# 4-IN-OPTPO-4-OUT.net
KiCad netlist of a schematic drawn in EAGLE
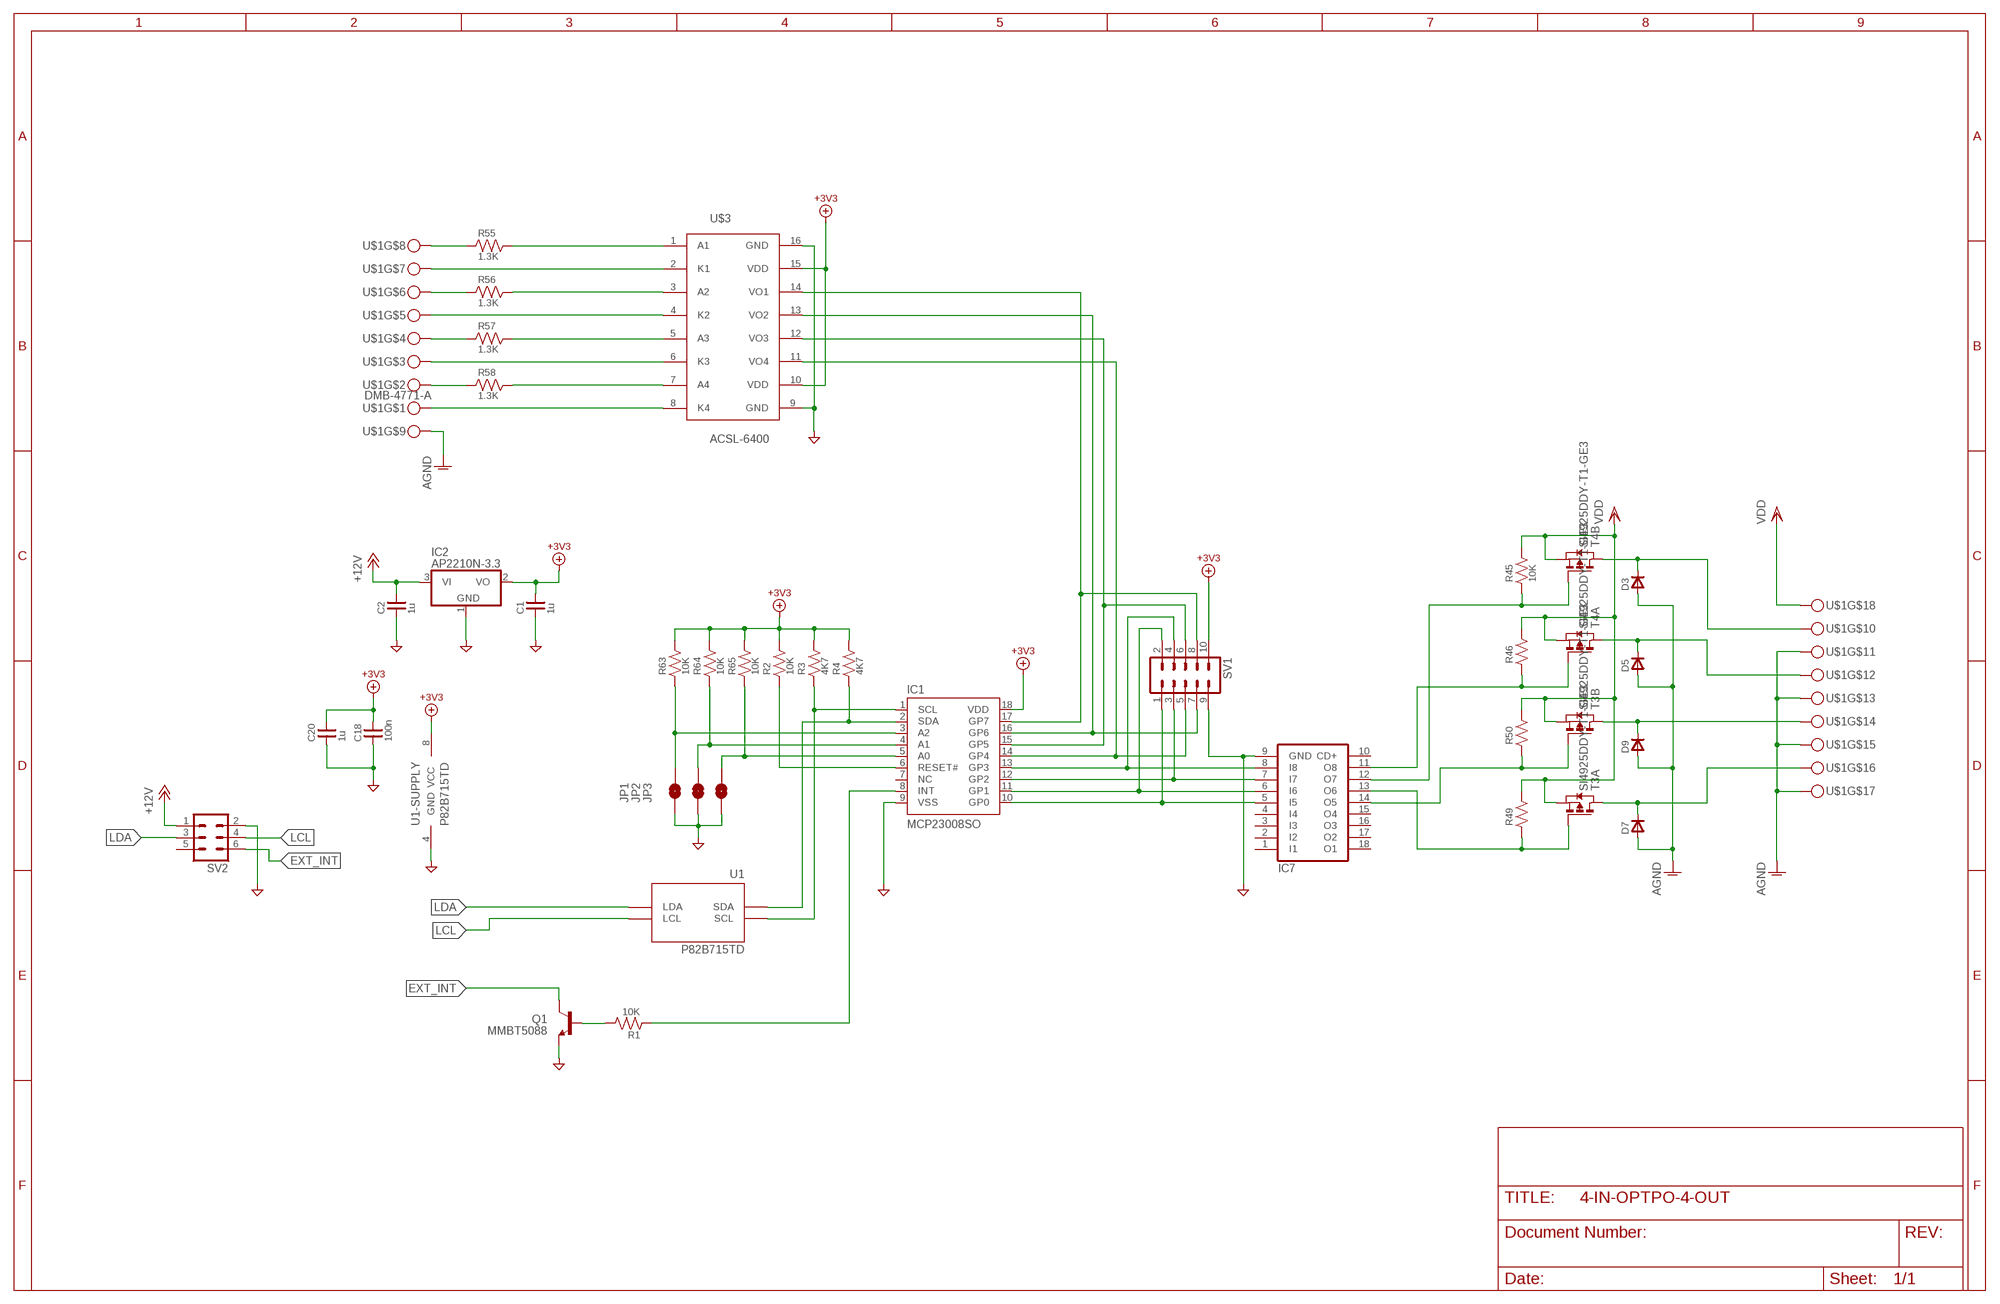
[diagram p0: schematic, sheet 1]

(export (version "E")
  (design (tool "Eeschema 10.0.6"))
  (components
    (comp (ref "C1")
      (value "1u")
      (footprint "eagle-import:C0805")
      (libsource (lib "eagle-import") (part "C0805"))
    )
    (comp (ref "C2")
      (value "1u")
      (footprint "eagle-import:C0805")
      (libsource (lib "eagle-import") (part "C0805"))
    )
    (comp (ref "C18")
      (value "100n")
      (footprint "eagle-import:C0805")
      (libsource (lib "eagle-import") (part "C0805"))
    )
    (comp (ref "C20")
      (value "1u")
      (footprint "eagle-import:C0805")
      (libsource (lib "eagle-import") (part "C0805"))
    )
    (comp (ref "D3")
      (value "DSMA")
      (footprint "eagle-import:DSMA")
      (libsource (lib "eagle-import") (part "DSMA"))
    )
    (comp (ref "D5")
      (value "DSMA")
      (footprint "eagle-import:DSMA")
      (libsource (lib "eagle-import") (part "DSMA"))
    )
    (comp (ref "D7")
      (value "DSMA")
      (footprint "eagle-import:DSMA")
      (libsource (lib "eagle-import") (part "DSMA"))
    )
    (comp (ref "D9")
      (value "DSMA")
      (footprint "eagle-import:DSMA")
      (libsource (lib "eagle-import") (part "DSMA"))
    )
    (comp (ref "IC1")
      (value "MCP23008SO")
      (footprint "eagle-import:SO-18W")
      (libsource (lib "eagle-import") (part "MCP23008SO"))
    )
    (comp (ref "IC2")
      (value "AP2210N-3.3")
      (footprint "eagle-import:SOT23")
      (libsource (lib "eagle-import") (part "MCP1703CB"))
    )
    (comp (ref "IC7")
      (value "ULN2803A")
      (footprint "eagle-import:SO18W")
      (libsource (lib "eagle-import") (part "ULN2803A"))
    )
    (comp (ref "JP1")
      (value "JUMPER-PAD-2-NOYES_SILK")
      (footprint "eagle-import:PAD-JUMPER-2-NO_YES_SILK")
      (libsource (lib "eagle-import") (part "JUMPER-PAD-2-NOYES_SILK"))
    )
    (comp (ref "JP2")
      (value "JUMPER-PAD-2-NOYES_SILK")
      (footprint "eagle-import:PAD-JUMPER-2-NO_YES_SILK")
      (libsource (lib "eagle-import") (part "JUMPER-PAD-2-NOYES_SILK"))
    )
    (comp (ref "JP3")
      (value "JUMPER-PAD-2-NOYES_SILK")
      (footprint "eagle-import:PAD-JUMPER-2-NO_YES_SILK")
      (libsource (lib "eagle-import") (part "JUMPER-PAD-2-NOYES_SILK"))
    )
    (comp (ref "Q1")
      (value "MMBT5088")
      (footprint "eagle-import:SOT23-3")
      (libsource (lib "eagle-import") (part "TRANSISTOR_NPNMMBT5088"))
    )
    (comp (ref "R1")
      (value "10K")
      (footprint "eagle-import:R0805")
      (libsource (lib "eagle-import") (part "RU0805"))
    )
    (comp (ref "R2")
      (value "10K")
      (footprint "eagle-import:R0805")
      (libsource (lib "eagle-import") (part "RU0805"))
    )
    (comp (ref "R3")
      (value "4K7")
      (footprint "eagle-import:R0805")
      (libsource (lib "eagle-import") (part "RU0805"))
    )
    (comp (ref "R4")
      (value "4K7")
      (footprint "eagle-import:R0805")
      (libsource (lib "eagle-import") (part "RU0805"))
    )
    (comp (ref "R45")
      (value "10K")
      (footprint "eagle-import:R0805")
      (libsource (lib "eagle-import") (part "RU0805"))
    )
    (comp (ref "R46")
      (value "RU0805")
      (footprint "eagle-import:R0805")
      (libsource (lib "eagle-import") (part "RU0805"))
    )
    (comp (ref "R49")
      (value "RU0805")
      (footprint "eagle-import:R0805")
      (libsource (lib "eagle-import") (part "RU0805"))
    )
    (comp (ref "R50")
      (value "RU0805")
      (footprint "eagle-import:R0805")
      (libsource (lib "eagle-import") (part "RU0805"))
    )
    (comp (ref "R55")
      (value "1.3K")
      (footprint "eagle-import:R0805")
      (libsource (lib "eagle-import") (part "RU0805"))
    )
    (comp (ref "R56")
      (value "1.3K")
      (footprint "eagle-import:R0805")
      (libsource (lib "eagle-import") (part "RU0805"))
    )
    (comp (ref "R57")
      (value "1.3K")
      (footprint "eagle-import:R0805")
      (libsource (lib "eagle-import") (part "RU0805"))
    )
    (comp (ref "R58")
      (value "1.3K")
      (footprint "eagle-import:R0805")
      (libsource (lib "eagle-import") (part "RU0805"))
    )
    (comp (ref "R63")
      (value "10K")
      (footprint "eagle-import:R0805")
      (libsource (lib "eagle-import") (part "RU0805"))
    )
    (comp (ref "R64")
      (value "10K")
      (footprint "eagle-import:R0805")
      (libsource (lib "eagle-import") (part "RU0805"))
    )
    (comp (ref "R65")
      (value "10K")
      (footprint "eagle-import:R0805")
      (libsource (lib "eagle-import") (part "RU0805"))
    )
    (comp (ref "SV1")
      (value "ML10")
      (footprint "eagle-import:ML10")
      (libsource (lib "eagle-import") (part "ML10"))
    )
    (comp (ref "SV2")
      (value "ML6")
      (footprint "eagle-import:ML6")
      (libsource (lib "eagle-import") (part "ML6"))
    )
    (comp (ref "T3")
      (value "SI4925DDY-T1-GE3")
      (footprint "eagle-import:SO8")
      (libsource (lib "eagle-import") (part "PMOS2SO8"))
    )
    (comp (ref "T4")
      (value "SI4925DDY-T1-GE3")
      (footprint "eagle-import:SO8")
      (libsource (lib "eagle-import") (part "PMOS2SO8"))
    )
    (comp (ref "U$1")
      (value "DMB-4771-A")
      (footprint "eagle-import:DMB-4771-A-PKG")
      (libsource (lib "eagle-import") (part "DMB-4771-A"))
    )
    (comp (ref "U$3")
      (value "ACSL-6400")
      (footprint "eagle-import:SO16")
      (libsource (lib "eagle-import") (part "ACSL-6400"))
    )
    (comp (ref "U1")
      (value "P82B715TD")
      (footprint "eagle-import:SOIC-8")
      (fields (field (name "MANUFACTURER") "NXP Semiconductors") (field (name "PART_NUMBER") "P82B715TD,118"))
      (libsource (lib "eagle-import") (part "P82B715?TD"))
    )
  )
  (nets
    (net (code "1") (name "+12V") (class "Default")
      (node (ref "C2") (pin "2") (pinfunction "2_2") (pintype "passive"))
      (node (ref "IC2") (pin "3") (pinfunction "VI_3") (pintype "input"))
      (node (ref "SV2") (pin "1") (pinfunction "1_1") (pintype "passive"))
    )
    (net (code "2") (name "AGND") (class "Default")
      (node (ref "D3") (pin "A") (pinfunction "A_A") (pintype "passive"))
      (node (ref "D5") (pin "A") (pinfunction "A_A") (pintype "passive"))
      (node (ref "D7") (pin "A") (pinfunction "A_A") (pintype "passive"))
      (node (ref "D9") (pin "A") (pinfunction "A_A") (pintype "passive"))
      (node (ref "U$1") (pin "P$11") (pinfunction "KL_P$11") (pintype "passive"))
      (node (ref "U$1") (pin "P$13") (pinfunction "KL_P$13") (pintype "passive"))
      (node (ref "U$1") (pin "P$15") (pinfunction "KL_P$15") (pintype "passive"))
      (node (ref "U$1") (pin "P$17") (pinfunction "KL_P$17") (pintype "passive"))
      (node (ref "U$1") (pin "P$9") (pinfunction "KL_P$9") (pintype "passive"))
    )
    (net (code "3") (name "EXT_INT") (class "Default")
      (node (ref "Q1") (pin "3") (pinfunction "C_3") (pintype "passive"))
      (node (ref "SV2") (pin "6") (pinfunction "6_6") (pintype "passive"))
    )
    (net (code "4") (name "LCL") (class "Default")
      (node (ref "SV2") (pin "4") (pinfunction "4_4") (pintype "passive"))
      (node (ref "U1") (pin "2") (pinfunction "LCL_2") (pintype "bidirectional"))
    )
    (net (code "5") (name "LDA") (class "Default")
      (node (ref "SV2") (pin "3") (pinfunction "3_3") (pintype "passive"))
      (node (ref "U1") (pin "7") (pinfunction "LDA_7") (pintype "bidirectional"))
    )
    (net (code "6") (name "Net-(IC1-A0)") (class "Default")
      (node (ref "IC1") (pin "5") (pinfunction "A0_5") (pintype "input"))
      (node (ref "JP3") (pin "2") (pinfunction "2_2") (pintype "passive"))
      (node (ref "R65") (pin "1") (pinfunction "1_1") (pintype "passive"))
    )
    (net (code "7") (name "Net-(IC1-A1)") (class "Default")
      (node (ref "IC1") (pin "4") (pinfunction "A1_4") (pintype "input"))
      (node (ref "JP2") (pin "2") (pinfunction "2_2") (pintype "passive"))
      (node (ref "R64") (pin "1") (pinfunction "1_1") (pintype "passive"))
    )
    (net (code "8") (name "Net-(IC1-A2)") (class "Default")
      (node (ref "IC1") (pin "3") (pinfunction "A2_3") (pintype "input"))
      (node (ref "JP1") (pin "2") (pinfunction "2_2") (pintype "passive"))
      (node (ref "R63") (pin "1") (pinfunction "1_1") (pintype "passive"))
    )
    (net (code "9") (name "Net-(IC1-GP0)") (class "Default")
      (node (ref "IC1") (pin "10") (pinfunction "GP0_10") (pintype "bidirectional"))
      (node (ref "IC7") (pin "5") (pinfunction "I5_5") (pintype "input"))
      (node (ref "SV1") (pin "1") (pinfunction "1_1") (pintype "passive"))
    )
    (net (code "10") (name "Net-(IC1-GP1)") (class "Default")
      (node (ref "IC1") (pin "11") (pinfunction "GP1_11") (pintype "bidirectional"))
      (node (ref "IC7") (pin "6") (pinfunction "I6_6") (pintype "input"))
      (node (ref "SV1") (pin "2") (pinfunction "2_2") (pintype "passive"))
    )
    (net (code "11") (name "Net-(IC1-GP2)") (class "Default")
      (node (ref "IC1") (pin "12") (pinfunction "GP2_12") (pintype "bidirectional"))
      (node (ref "IC7") (pin "7") (pinfunction "I7_7") (pintype "input"))
      (node (ref "SV1") (pin "3") (pinfunction "3_3") (pintype "passive"))
    )
    (net (code "12") (name "Net-(IC1-GP3)") (class "Default")
      (node (ref "IC1") (pin "13") (pinfunction "GP3_13") (pintype "bidirectional"))
      (node (ref "IC7") (pin "8") (pinfunction "I8_8") (pintype "input"))
      (node (ref "SV1") (pin "4") (pinfunction "4_4") (pintype "passive"))
    )
    (net (code "13") (name "Net-(IC1-GP4)") (class "Default")
      (node (ref "IC1") (pin "14") (pinfunction "GP4_14") (pintype "bidirectional"))
      (node (ref "SV1") (pin "5") (pinfunction "5_5") (pintype "passive"))
      (node (ref "U$3") (pin "11") (pinfunction "VO4_11") (pintype "bidirectional"))
    )
    (net (code "14") (name "Net-(IC1-GP5)") (class "Default")
      (node (ref "IC1") (pin "15") (pinfunction "GP5_15") (pintype "bidirectional"))
      (node (ref "SV1") (pin "6") (pinfunction "6_6") (pintype "passive"))
      (node (ref "U$3") (pin "12") (pinfunction "VO3_12") (pintype "bidirectional"))
    )
    (net (code "15") (name "Net-(IC1-GP6)") (class "Default")
      (node (ref "IC1") (pin "16") (pinfunction "GP6_16") (pintype "bidirectional"))
      (node (ref "SV1") (pin "7") (pinfunction "7_7") (pintype "passive"))
      (node (ref "U$3") (pin "13") (pinfunction "VO2_13") (pintype "bidirectional"))
    )
    (net (code "16") (name "Net-(IC1-GP7)") (class "Default")
      (node (ref "IC1") (pin "17") (pinfunction "GP7_17") (pintype "bidirectional"))
      (node (ref "SV1") (pin "8") (pinfunction "8_8") (pintype "passive"))
      (node (ref "U$3") (pin "14") (pinfunction "VO1_14") (pintype "bidirectional"))
    )
    (net (code "17") (name "Net-(IC1-INT)") (class "Default")
      (node (ref "IC1") (pin "8") (pinfunction "INT_8") (pintype "output"))
      (node (ref "R1") (pin "1") (pinfunction "1_1") (pintype "passive"))
    )
    (net (code "18") (name "Net-(IC1-RESET#)") (class "Default")
      (node (ref "IC1") (pin "6") (pinfunction "RESET#_6") (pintype "input"))
      (node (ref "R2") (pin "1") (pinfunction "1_1") (pintype "passive"))
    )
    (net (code "19") (name "Net-(IC1-SCL)") (class "Default")
      (node (ref "IC1") (pin "1") (pinfunction "SCL_1") (pintype "input"))
      (node (ref "R3") (pin "1") (pinfunction "1_1") (pintype "passive"))
      (node (ref "U1") (pin "3") (pinfunction "SCL_3") (pintype "bidirectional"))
    )
    (net (code "20") (name "Net-(IC1-SDA)") (class "Default")
      (node (ref "IC1") (pin "2") (pinfunction "SDA_2") (pintype "bidirectional"))
      (node (ref "R4") (pin "1") (pinfunction "1_1") (pintype "passive"))
      (node (ref "U1") (pin "6") (pinfunction "SDA_6") (pintype "bidirectional"))
    )
    (net (code "21") (name "Net-(IC7-O5)") (class "Default")
      (node (ref "IC7") (pin "14") (pinfunction "O5_14") (pintype "open_collector"))
      (node (ref "R50") (pin "1") (pinfunction "1_1") (pintype "passive"))
      (node (ref "T3") (pin "4") (pinfunction "G_4") (pintype "passive"))
    )
    (net (code "22") (name "Net-(IC7-O6)") (class "Default")
      (node (ref "IC7") (pin "13") (pinfunction "O6_13") (pintype "open_collector"))
      (node (ref "R49") (pin "1") (pinfunction "1_1") (pintype "passive"))
      (node (ref "T3") (pin "2") (pinfunction "G_2") (pintype "passive"))
    )
    (net (code "23") (name "Net-(IC7-O7)") (class "Default")
      (node (ref "IC7") (pin "12") (pinfunction "O7_12") (pintype "open_collector"))
      (node (ref "R45") (pin "1") (pinfunction "1_1") (pintype "passive"))
      (node (ref "T4") (pin "4") (pinfunction "G_4") (pintype "passive"))
    )
    (net (code "24") (name "Net-(IC7-O8)") (class "Default")
      (node (ref "IC7") (pin "11") (pinfunction "O8_11") (pintype "open_collector"))
      (node (ref "R46") (pin "1") (pinfunction "1_1") (pintype "passive"))
      (node (ref "T4") (pin "2") (pinfunction "G_2") (pintype "passive"))
    )
    (net (code "25") (name "Net-(Q1-B)") (class "Default")
      (node (ref "Q1") (pin "1") (pinfunction "B_1") (pintype "passive"))
      (node (ref "R1") (pin "2") (pinfunction "2_2") (pintype "passive"))
    )
    (net (code "26") (name "Net-(U$1A-KL)") (class "Default")
      (node (ref "U$1") (pin "P$1") (pinfunction "KL_P$1") (pintype "passive"))
      (node (ref "U$3") (pin "8") (pinfunction "K4_8") (pintype "input"))
    )
    (net (code "27") (name "Net-(U$1B-KL)") (class "Default")
      (node (ref "D3") (pin "C") (pinfunction "C_C") (pintype "passive"))
      (node (ref "T4") (pin "5") (pinfunction "D_5") (pintype "passive"))
      (node (ref "T4") (pin "6") (pinfunction "D_6") (pintype "passive"))
      (node (ref "U$1") (pin "P$10") (pinfunction "KL_P$10") (pintype "passive"))
    )
    (net (code "28") (name "Net-(U$1D-KL)") (class "Default")
      (node (ref "D5") (pin "C") (pinfunction "C_C") (pintype "passive"))
      (node (ref "T4") (pin "7") (pinfunction "D_7") (pintype "passive"))
      (node (ref "T4") (pin "8") (pinfunction "D_8") (pintype "passive"))
      (node (ref "U$1") (pin "P$12") (pinfunction "KL_P$12") (pintype "passive"))
    )
    (net (code "29") (name "Net-(U$1F-KL)") (class "Default")
      (node (ref "D9") (pin "C") (pinfunction "C_C") (pintype "passive"))
      (node (ref "T3") (pin "5") (pinfunction "D_5") (pintype "passive"))
      (node (ref "T3") (pin "6") (pinfunction "D_6") (pintype "passive"))
      (node (ref "U$1") (pin "P$14") (pinfunction "KL_P$14") (pintype "passive"))
    )
    (net (code "30") (name "Net-(U$1H-KL)") (class "Default")
      (node (ref "D7") (pin "C") (pinfunction "C_C") (pintype "passive"))
      (node (ref "T3") (pin "7") (pinfunction "D_7") (pintype "passive"))
      (node (ref "T3") (pin "8") (pinfunction "D_8") (pintype "passive"))
      (node (ref "U$1") (pin "P$16") (pinfunction "KL_P$16") (pintype "passive"))
    )
    (net (code "31") (name "Net-(U$1K-KL)") (class "Default")
      (node (ref "R58") (pin "1") (pinfunction "1_1") (pintype "passive"))
      (node (ref "U$1") (pin "P$2") (pinfunction "KL_P$2") (pintype "passive"))
    )
    (net (code "32") (name "Net-(U$1L-KL)") (class "Default")
      (node (ref "U$1") (pin "P$3") (pinfunction "KL_P$3") (pintype "passive"))
      (node (ref "U$3") (pin "6") (pinfunction "K3_6") (pintype "input"))
    )
    (net (code "33") (name "Net-(U$1M-KL)") (class "Default")
      (node (ref "R57") (pin "1") (pinfunction "1_1") (pintype "passive"))
      (node (ref "U$1") (pin "P$4") (pinfunction "KL_P$4") (pintype "passive"))
    )
    (net (code "34") (name "Net-(U$1N-KL)") (class "Default")
      (node (ref "U$1") (pin "P$5") (pinfunction "KL_P$5") (pintype "passive"))
      (node (ref "U$3") (pin "4") (pinfunction "K2_4") (pintype "input"))
    )
    (net (code "35") (name "Net-(U$1O-KL)") (class "Default")
      (node (ref "R56") (pin "1") (pinfunction "1_1") (pintype "passive"))
      (node (ref "U$1") (pin "P$6") (pinfunction "KL_P$6") (pintype "passive"))
    )
    (net (code "36") (name "Net-(U$1P-KL)") (class "Default")
      (node (ref "U$1") (pin "P$7") (pinfunction "KL_P$7") (pintype "passive"))
      (node (ref "U$3") (pin "2") (pinfunction "K1_2") (pintype "input"))
    )
    (net (code "37") (name "Net-(U$1Q-KL)") (class "Default")
      (node (ref "R55") (pin "1") (pinfunction "1_1") (pintype "passive"))
      (node (ref "U$1") (pin "P$8") (pinfunction "KL_P$8") (pintype "passive"))
    )
    (net (code "38") (name "Net-(U$3-A1)") (class "Default")
      (node (ref "R55") (pin "2") (pinfunction "2_2") (pintype "passive"))
      (node (ref "U$3") (pin "1") (pinfunction "A1_1") (pintype "input"))
    )
    (net (code "39") (name "Net-(U$3-A2)") (class "Default")
      (node (ref "R56") (pin "2") (pinfunction "2_2") (pintype "passive"))
      (node (ref "U$3") (pin "3") (pinfunction "A2_3") (pintype "input"))
    )
    (net (code "40") (name "Net-(U$3-A3)") (class "Default")
      (node (ref "R57") (pin "2") (pinfunction "2_2") (pintype "passive"))
      (node (ref "U$3") (pin "5") (pinfunction "A3_5") (pintype "input"))
    )
    (net (code "41") (name "Net-(U$3-A4)") (class "Default")
      (node (ref "R58") (pin "2") (pinfunction "2_2") (pintype "passive"))
      (node (ref "U$3") (pin "7") (pinfunction "A4_7") (pintype "input"))
    )
    (net (code "42") (name "V+3V3") (class "Default")
      (node (ref "C1") (pin "2") (pinfunction "2_2") (pintype "passive"))
      (node (ref "C18") (pin "2") (pinfunction "2_2") (pintype "passive"))
      (node (ref "C20") (pin "2") (pinfunction "2_2") (pintype "passive"))
      (node (ref "IC1") (pin "18") (pinfunction "VDD_18") (pintype "power_in"))
      (node (ref "IC2") (pin "2") (pinfunction "VO_2") (pintype "passive"))
      (node (ref "R2") (pin "2") (pinfunction "2_2") (pintype "passive"))
      (node (ref "R3") (pin "2") (pinfunction "2_2") (pintype "passive"))
      (node (ref "R4") (pin "2") (pinfunction "2_2") (pintype "passive"))
      (node (ref "R63") (pin "2") (pinfunction "2_2") (pintype "passive"))
      (node (ref "R64") (pin "2") (pinfunction "2_2") (pintype "passive"))
      (node (ref "R65") (pin "2") (pinfunction "2_2") (pintype "passive"))
      (node (ref "SV1") (pin "10") (pinfunction "10_10") (pintype "passive"))
      (node (ref "U$3") (pin "10") (pinfunction "VDD_10") (pintype "power_in"))
      (node (ref "U$3") (pin "15") (pinfunction "VDD_15") (pintype "power_in"))
      (node (ref "U1") (pin "8") (pinfunction "VCC_8") (pintype "bidirectional"))
    )
    (net (code "43") (name "VDD") (class "Default")
      (node (ref "R45") (pin "2") (pinfunction "2_2") (pintype "passive"))
      (node (ref "R46") (pin "2") (pinfunction "2_2") (pintype "passive"))
      (node (ref "R49") (pin "2") (pinfunction "2_2") (pintype "passive"))
      (node (ref "R50") (pin "2") (pinfunction "2_2") (pintype "passive"))
      (node (ref "T3") (pin "1") (pinfunction "S_1") (pintype "passive"))
      (node (ref "T3") (pin "3") (pinfunction "S_3") (pintype "passive"))
      (node (ref "T4") (pin "1") (pinfunction "S_1") (pintype "passive"))
      (node (ref "T4") (pin "3") (pinfunction "S_3") (pintype "passive"))
      (node (ref "U$1") (pin "P$18") (pinfunction "KL_P$18") (pintype "passive"))
    )
    (net (code "44") (name "VDG") (class "Default")
      (node (ref "C1") (pin "1") (pinfunction "1_1") (pintype "passive"))
      (node (ref "C18") (pin "1") (pinfunction "1_1") (pintype "passive"))
      (node (ref "C2") (pin "1") (pinfunction "1_1") (pintype "passive"))
      (node (ref "C20") (pin "1") (pinfunction "1_1") (pintype "passive"))
      (node (ref "IC1") (pin "9") (pinfunction "VSS_9") (pintype "power_in"))
      (node (ref "IC2") (pin "1") (pinfunction "GND_1") (pintype "passive"))
      (node (ref "IC7") (pin "9") (pinfunction "GND_9") (pintype "power_in"))
      (node (ref "JP1") (pin "1") (pinfunction "1_1") (pintype "passive"))
      (node (ref "JP2") (pin "1") (pinfunction "1_1") (pintype "passive"))
      (node (ref "JP3") (pin "1") (pinfunction "1_1") (pintype "passive"))
      (node (ref "Q1") (pin "2") (pinfunction "E_2") (pintype "passive"))
      (node (ref "SV1") (pin "9") (pinfunction "9_9") (pintype "passive"))
      (node (ref "SV2") (pin "2") (pinfunction "2_2") (pintype "passive"))
      (node (ref "U$3") (pin "16") (pinfunction "GND_16") (pintype "power_in"))
      (node (ref "U$3") (pin "9") (pinfunction "GND_9") (pintype "power_in"))
      (node (ref "U1") (pin "4") (pinfunction "GND_4") (pintype "bidirectional"))
    )
    (net (code "45") (name "unconnected-(IC1-NC-Pad7)") (class "Default")
      (node (ref "IC1") (pin "7") (pinfunction "NC_7") (pintype "no_connect"))
    )
    (net (code "46") (name "unconnected-(IC7-CD+-Pad10)") (class "Default")
      (node (ref "IC7") (pin "10") (pinfunction "CD+_10") (pintype "passive"))
    )
    (net (code "47") (name "unconnected-(IC7-I1-Pad1)") (class "Default")
      (node (ref "IC7") (pin "1") (pinfunction "I1_1") (pintype "input"))
    )
    (net (code "48") (name "unconnected-(IC7-I2-Pad2)") (class "Default")
      (node (ref "IC7") (pin "2") (pinfunction "I2_2") (pintype "input"))
    )
    (net (code "49") (name "unconnected-(IC7-I3-Pad3)") (class "Default")
      (node (ref "IC7") (pin "3") (pinfunction "I3_3") (pintype "input"))
    )
    (net (code "50") (name "unconnected-(IC7-I4-Pad4)") (class "Default")
      (node (ref "IC7") (pin "4") (pinfunction "I4_4") (pintype "input"))
    )
    (net (code "51") (name "unconnected-(IC7-O1-Pad18)") (class "Default")
      (node (ref "IC7") (pin "18") (pinfunction "O1_18") (pintype "open_collector"))
    )
    (net (code "52") (name "unconnected-(IC7-O2-Pad17)") (class "Default")
      (node (ref "IC7") (pin "17") (pinfunction "O2_17") (pintype "open_collector"))
    )
    (net (code "53") (name "unconnected-(IC7-O3-Pad16)") (class "Default")
      (node (ref "IC7") (pin "16") (pinfunction "O3_16") (pintype "open_collector"))
    )
    (net (code "54") (name "unconnected-(IC7-O4-Pad15)") (class "Default")
      (node (ref "IC7") (pin "15") (pinfunction "O4_15") (pintype "open_collector"))
    )
    (net (code "55") (name "unconnected-(SV2-Pad5)") (class "Default")
      (node (ref "SV2") (pin "5") (pinfunction "5_5") (pintype "passive"))
    )
  )
)
